# 2layer_shunt_test_2x.net
KiCad netlist of a schematic drawn in EAGLE
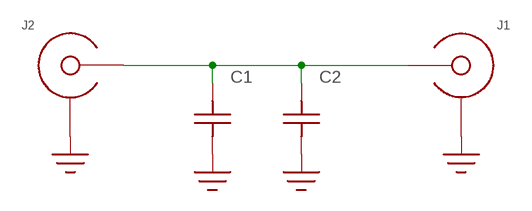
[diagram p0: schematic, sheet 1]

(export (version "E")
  (design (tool "Eeschema 10.0.6"))
  (components
    (comp (ref "C1")
      (value "C0603")
      (footprint "eagle-import:C0603")
      (libsource (lib "eagle-import") (part "C0603"))
    )
    (comp (ref "C2") (value "C") (footprint "eagle-import:C0402") (libsource (lib "eagle-import") (part "C")))
    (comp (ref "J1")
      (value "SMA_END_LAUNCH2L")
      (footprint "eagle-import:SMA_EDGE_LAUNCH_2L")
      (libsource (lib "eagle-import") (part "SMA_END_LAUNCH2L"))
    )
    (comp (ref "J2")
      (value "SMA_END_LAUNCH2L")
      (footprint "eagle-import:SMA_EDGE_LAUNCH_2L")
      (libsource (lib "eagle-import") (part "SMA_END_LAUNCH2L"))
    )
  )
  (nets
    (net (code "1") (name "GND") (class "Default")
      (node (ref "C1") (pin "P$1") (pinfunction "P$1_P$1") (pintype "bidirectional"))
      (node (ref "C2") (pin "1") (pinfunction "P$1_1") (pintype "bidirectional"))
      (node (ref "J1") (pin "BOTTOM_GND") (pinfunction "SHIELD_BOTTOM_GND") (pintype "bidirectional"))
      (node (ref "J1") (pin "GND@1") (pinfunction "SHIELD_GND@1") (pintype "bidirectional"))
      (node (ref "J1") (pin "GND@11") (pinfunction "SHIELD_GND@11") (pintype "bidirectional"))
      (node (ref "J1") (pin "GND@12") (pinfunction "SHIELD_GND@12") (pintype "bidirectional"))
      (node (ref "J1") (pin "GND@14") (pinfunction "SHIELD_GND@14") (pintype "bidirectional"))
      (node (ref "J1") (pin "GND@15") (pinfunction "SHIELD_GND@15") (pintype "bidirectional"))
      (node (ref "J1") (pin "GND@16") (pinfunction "SHIELD_GND@16") (pintype "bidirectional"))
      (node (ref "J1") (pin "GND@17") (pinfunction "SHIELD_GND@17") (pintype "bidirectional"))
      (node (ref "J1") (pin "GND@2") (pinfunction "SHIELD_GND@2") (pintype "bidirectional"))
      (node (ref "J1") (pin "GND@3") (pinfunction "SHIELD_GND@3") (pintype "bidirectional"))
      (node (ref "J1") (pin "GND@4") (pinfunction "SHIELD_GND@4") (pintype "bidirectional"))
      (node (ref "J1") (pin "GND@5") (pinfunction "SHIELD_GND@5") (pintype "bidirectional"))
      (node (ref "J1") (pin "GND@6") (pinfunction "SHIELD_GND@6") (pintype "bidirectional"))
      (node (ref "J1") (pin "GND@7") (pinfunction "SHIELD_GND@7") (pintype "bidirectional"))
      (node (ref "J1") (pin "GND@8") (pinfunction "SHIELD_GND@8") (pintype "bidirectional"))
      (node (ref "J1") (pin "GND_PAD1") (pinfunction "SHIELD_GND_PAD1") (pintype "bidirectional"))
      (node (ref "J1") (pin "GND_PAD2") (pinfunction "SHIELD_GND_PAD2") (pintype "bidirectional"))
      (node (ref "J2") (pin "BOTTOM_GND") (pinfunction "SHIELD_BOTTOM_GND") (pintype "bidirectional"))
      (node (ref "J2") (pin "GND@1") (pinfunction "SHIELD_GND@1") (pintype "bidirectional"))
      (node (ref "J2") (pin "GND@11") (pinfunction "SHIELD_GND@11") (pintype "bidirectional"))
      (node (ref "J2") (pin "GND@12") (pinfunction "SHIELD_GND@12") (pintype "bidirectional"))
      (node (ref "J2") (pin "GND@14") (pinfunction "SHIELD_GND@14") (pintype "bidirectional"))
      (node (ref "J2") (pin "GND@15") (pinfunction "SHIELD_GND@15") (pintype "bidirectional"))
      (node (ref "J2") (pin "GND@16") (pinfunction "SHIELD_GND@16") (pintype "bidirectional"))
      (node (ref "J2") (pin "GND@17") (pinfunction "SHIELD_GND@17") (pintype "bidirectional"))
      (node (ref "J2") (pin "GND@2") (pinfunction "SHIELD_GND@2") (pintype "bidirectional"))
      (node (ref "J2") (pin "GND@3") (pinfunction "SHIELD_GND@3") (pintype "bidirectional"))
      (node (ref "J2") (pin "GND@4") (pinfunction "SHIELD_GND@4") (pintype "bidirectional"))
      (node (ref "J2") (pin "GND@5") (pinfunction "SHIELD_GND@5") (pintype "bidirectional"))
      (node (ref "J2") (pin "GND@6") (pinfunction "SHIELD_GND@6") (pintype "bidirectional"))
      (node (ref "J2") (pin "GND@7") (pinfunction "SHIELD_GND@7") (pintype "bidirectional"))
      (node (ref "J2") (pin "GND@8") (pinfunction "SHIELD_GND@8") (pintype "bidirectional"))
      (node (ref "J2") (pin "GND_PAD1") (pinfunction "SHIELD_GND_PAD1") (pintype "bidirectional"))
      (node (ref "J2") (pin "GND_PAD2") (pinfunction "SHIELD_GND_PAD2") (pintype "bidirectional"))
    )
    (net (code "2") (name "Net-(C2-P$2)") (class "Default")
      (node (ref "C1") (pin "P$2") (pinfunction "P$2_P$2") (pintype "bidirectional"))
      (node (ref "C2") (pin "2") (pinfunction "P$2_2") (pintype "bidirectional"))
      (node (ref "J1") (pin "CENTER@1") (pinfunction "CENTER_CENTER@1") (pintype "bidirectional"))
      (node (ref "J2") (pin "CENTER@1") (pinfunction "CENTER_CENTER@1") (pintype "bidirectional"))
    )
  )
)
